# design.net
KiCad netlist of a schematic drawn in Altium Designer
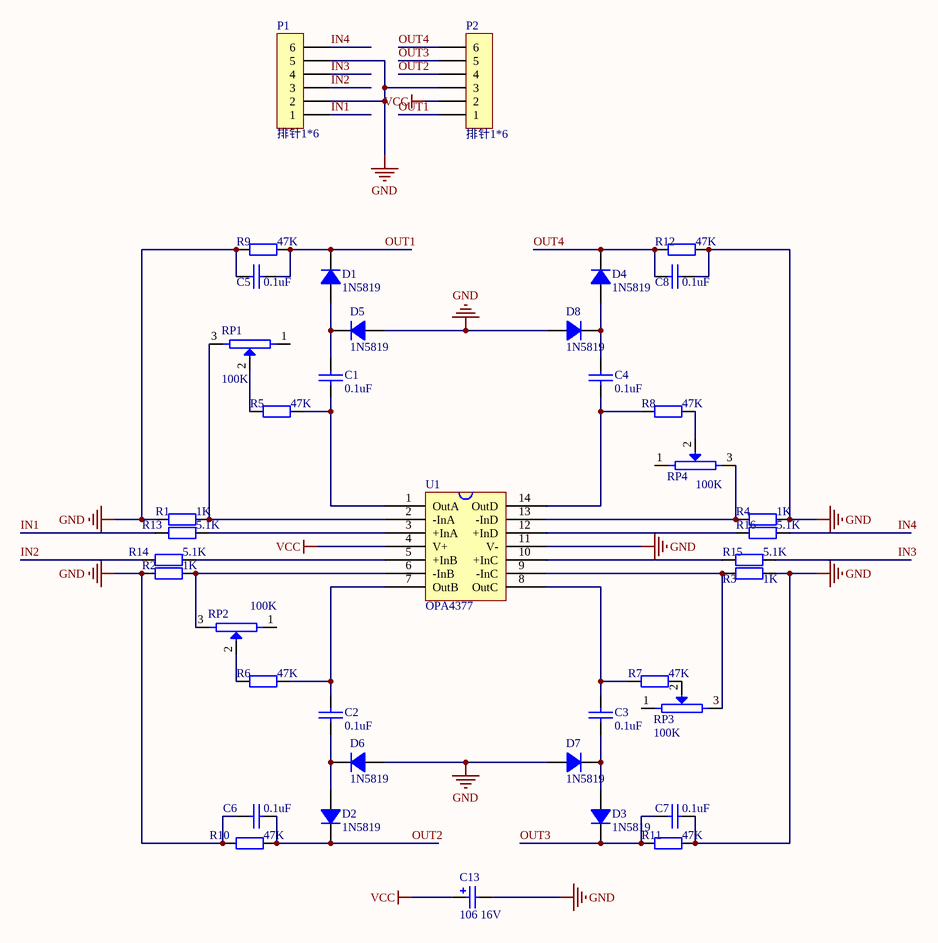
[diagram p0: 运放原理图.SchDoc]

(export (version "E")
  (design (tool "Eeschema 10.0.6"))
  (components
    (comp (ref "C1")
      (value "0.1uF")
      (footprint "C0805")
      (description "Capacitor")
      (libsource (lib "运放原理图库") (part "普通电容"))
    )
    (comp (ref "C2")
      (value "0.1uF")
      (footprint "C0805")
      (description "Capacitor")
      (libsource (lib "运放原理图库") (part "普通电容"))
    )
    (comp (ref "C3")
      (value "0.1uF")
      (footprint "C0805")
      (description "Capacitor")
      (libsource (lib "运放原理图库") (part "普通电容"))
    )
    (comp (ref "C4")
      (value "0.1uF")
      (footprint "C0805")
      (description "Capacitor")
      (libsource (lib "运放原理图库") (part "普通电容"))
    )
    (comp (ref "C5")
      (value "0.1uF")
      (footprint "C0805")
      (description "Capacitor")
      (libsource (lib "运放原理图库") (part "普通电容"))
    )
    (comp (ref "C6")
      (value "0.1uF")
      (footprint "C0805")
      (description "Capacitor")
      (libsource (lib "运放原理图库") (part "普通电容"))
    )
    (comp (ref "C7")
      (value "0.1uF")
      (footprint "C0805")
      (description "Capacitor")
      (libsource (lib "运放原理图库") (part "普通电容"))
    )
    (comp (ref "C8")
      (value "0.1uF")
      (footprint "C0805")
      (description "Capacitor")
      (libsource (lib "运放原理图库") (part "普通电容"))
    )
    (comp (ref "C13") (value "106 16V") (footprint "Tan-A3216") (libsource (lib "运放原理图库") (part "钽电容")))
    (comp (ref "D1")
      (value "1N5819")
      (footprint "SOD-123")
      (description "1N5819 二极管 Diode")
      (fields (field (name "PUBLISHER") "Altium Limited"))
      (libsource (lib "运放原理图库") (part "1N5819"))
    )
    (comp (ref "D2")
      (value "1N5819")
      (footprint "SOD-123")
      (description "1N5819 二极管 Diode")
      (fields (field (name "PUBLISHER") "Altium Limited"))
      (libsource (lib "运放原理图库") (part "1N5819"))
    )
    (comp (ref "D3")
      (value "1N5819")
      (footprint "SOD-123")
      (description "1N5819 二极管 Diode")
      (fields (field (name "PUBLISHER") "Altium Limited"))
      (libsource (lib "运放原理图库") (part "1N5819"))
    )
    (comp (ref "D4")
      (value "1N5819")
      (footprint "SOD-123")
      (description "1N5819 二极管 Diode")
      (fields (field (name "PUBLISHER") "Altium Limited"))
      (libsource (lib "运放原理图库") (part "1N5819"))
    )
    (comp (ref "D5")
      (value "1N5819")
      (footprint "SOD-123")
      (description "1N5819 二极管 Diode")
      (fields (field (name "PUBLISHER") "Altium Limited"))
      (libsource (lib "运放原理图库") (part "1N5819"))
    )
    (comp (ref "D6")
      (value "1N5819")
      (footprint "SOD-123")
      (description "1N5819 二极管 Diode")
      (fields (field (name "PUBLISHER") "Altium Limited"))
      (libsource (lib "运放原理图库") (part "1N5819"))
    )
    (comp (ref "D7")
      (value "1N5819")
      (footprint "SOD-123")
      (description "1N5819 二极管 Diode")
      (fields (field (name "PUBLISHER") "Altium Limited"))
      (libsource (lib "运放原理图库") (part "1N5819"))
    )
    (comp (ref "D8")
      (value "1N5819")
      (footprint "SOD-123")
      (description "1N5819 二极管 Diode")
      (fields (field (name "PUBLISHER") "Altium Limited"))
      (libsource (lib "运放原理图库") (part "1N5819"))
    )
    (comp (ref "P1")
      (value "排针1*6")
      (footprint "LQ_SIP6")
      (description "Connector")
      (libsource (lib "运放原理图库") (part "CON6"))
    )
    (comp (ref "P2")
      (value "排针1*6")
      (footprint "LQ_SIP6")
      (description "Connector")
      (libsource (lib "") (part "CON6_1"))
    )
    (comp (ref "R1")
      (value "1K")
      (footprint "R0805")
      (description "Resistor")
      (fields (field (name "Comment") "1k") (field (name "PUBLISHER") "Altium Limited"))
      (libsource (lib "运放原理图库") (part "Res2"))
    )
    (comp (ref "R2")
      (value "1K")
      (footprint "R0805")
      (description "Resistor")
      (fields (field (name "Comment") "1k") (field (name "PUBLISHER") "Altium Limited"))
      (libsource (lib "运放原理图库") (part "Res2"))
    )
    (comp (ref "R3")
      (value "1K")
      (footprint "R0805")
      (description "Resistor")
      (fields (field (name "Comment") "1k") (field (name "PUBLISHER") "Altium Limited"))
      (libsource (lib "运放原理图库") (part "Res2"))
    )
    (comp (ref "R4")
      (value "1K")
      (footprint "R0805")
      (description "Resistor")
      (fields (field (name "Comment") "1k") (field (name "PUBLISHER") "Altium Limited"))
      (libsource (lib "运放原理图库") (part "Res2"))
    )
    (comp (ref "R5")
      (value "47K")
      (footprint "R0805")
      (description "Resistor")
      (fields (field (name "Comment") "47k") (field (name "PUBLISHER") "Altium Limited"))
      (libsource (lib "运放原理图库") (part "Res2"))
    )
    (comp (ref "R6")
      (value "47K")
      (footprint "R0805")
      (description "Resistor")
      (fields (field (name "Comment") "47k") (field (name "PUBLISHER") "Altium Limited"))
      (libsource (lib "运放原理图库") (part "Res2"))
    )
    (comp (ref "R7")
      (value "47K")
      (footprint "R0805")
      (description "Resistor")
      (fields (field (name "Comment") "47k") (field (name "PUBLISHER") "Altium Limited"))
      (libsource (lib "运放原理图库") (part "Res2"))
    )
    (comp (ref "R8")
      (value "47K")
      (footprint "R0805")
      (description "Resistor")
      (fields (field (name "Comment") "47k") (field (name "PUBLISHER") "Altium Limited"))
      (libsource (lib "运放原理图库") (part "Res2"))
    )
    (comp (ref "R9")
      (value "47K")
      (footprint "R0805")
      (description "Resistor")
      (fields (field (name "Comment") "47k") (field (name "PUBLISHER") "Altium Limited"))
      (libsource (lib "运放原理图库") (part "Res2"))
    )
    (comp (ref "R10")
      (value "47K")
      (footprint "R0805")
      (description "Resistor")
      (fields (field (name "Comment") "47k") (field (name "PUBLISHER") "Altium Limited"))
      (libsource (lib "运放原理图库") (part "Res2"))
    )
    (comp (ref "R11")
      (value "47K")
      (footprint "R0805")
      (description "Resistor")
      (fields (field (name "Comment") "47k") (field (name "PUBLISHER") "Altium Limited"))
      (libsource (lib "运放原理图库") (part "Res2"))
    )
    (comp (ref "R12")
      (value "47K")
      (footprint "R0805")
      (description "Resistor")
      (fields (field (name "Comment") "47k") (field (name "PUBLISHER") "Altium Limited"))
      (libsource (lib "运放原理图库") (part "Res2"))
    )
    (comp (ref "R13")
      (value "5.1K")
      (footprint "R0805")
      (description "Resistor")
      (fields (field (name "Comment") "5.1k") (field (name "PUBLISHER") "Altium Limited"))
      (libsource (lib "运放原理图库") (part "Res2"))
    )
    (comp (ref "R14")
      (value "5.1K")
      (footprint "R0805")
      (description "Resistor")
      (fields (field (name "Comment") "5.1k") (field (name "PUBLISHER") "Altium Limited"))
      (libsource (lib "运放原理图库") (part "Res2"))
    )
    (comp (ref "R15")
      (value "5.1K")
      (footprint "R0805")
      (description "Resistor")
      (fields (field (name "Comment") "5.1k") (field (name "PUBLISHER") "Altium Limited"))
      (libsource (lib "运放原理图库") (part "Res2"))
    )
    (comp (ref "R16")
      (value "5.1K")
      (footprint "R0805")
      (description "Resistor")
      (fields (field (name "Comment") "5.1k") (field (name "PUBLISHER") "Altium Limited"))
      (libsource (lib "运放原理图库") (part "Res2"))
    )
    (comp (ref "RP1")
      (value "100K")
      (footprint "电位器")
      (description "3端可调电阻")
      (libsource (lib "运放原理图库") (part "VR"))
    )
    (comp (ref "RP2")
      (value "100K")
      (footprint "电位器")
      (description "3端可调电阻")
      (libsource (lib "运放原理图库") (part "VR"))
    )
    (comp (ref "RP3")
      (value "100K")
      (footprint "电位器")
      (description "3端可调电阻")
      (libsource (lib "运放原理图库") (part "VR"))
    )
    (comp (ref "RP4")
      (value "100K")
      (footprint "电位器")
      (description "3端可调电阻")
      (libsource (lib "运放原理图库") (part "VR"))
    )
    (comp (ref "U1")
      (value "OPA4377")
      (footprint "TSSOP14")
      (description "OPA4377 四路轨对轨运放")
      (libsource (lib "运放原理图库") (part "OPA4377"))
    )
  )
  (nets
    (net (code "1") (name "/IN1") (class "Default")
      (node (ref "P1") (pin "1") (pinfunction "1_1") (pintype "passive"))
      (node (ref "R13") (pin "1") (pinfunction "1_1") (pintype "passive"))
    )
    (net (code "2") (name "/IN2") (class "Default")
      (node (ref "P1") (pin "3") (pinfunction "3_3") (pintype "passive"))
      (node (ref "R14") (pin "1") (pinfunction "1_1") (pintype "passive"))
    )
    (net (code "3") (name "/IN3") (class "Default")
      (node (ref "P1") (pin "4") (pinfunction "4_4") (pintype "passive"))
      (node (ref "R15") (pin "2") (pinfunction "2_2") (pintype "passive"))
    )
    (net (code "4") (name "/IN4") (class "Default")
      (node (ref "P1") (pin "6") (pinfunction "6_6") (pintype "passive"))
      (node (ref "R16") (pin "2") (pinfunction "2_2") (pintype "passive"))
    )
    (net (code "5") (name "/OUT1") (class "Default")
      (node (ref "C5") (pin "2") (pinfunction "2_2") (pintype "passive"))
      (node (ref "D1") (pin "K") (pinfunction "K_K") (pintype "passive"))
      (node (ref "P2") (pin "1") (pinfunction "1_1") (pintype "passive"))
      (node (ref "R9") (pin "2") (pinfunction "2_2") (pintype "passive"))
    )
    (net (code "6") (name "/OUT2") (class "Default")
      (node (ref "C6") (pin "1") (pinfunction "1_1") (pintype "passive"))
      (node (ref "D2") (pin "K") (pinfunction "K_K") (pintype "passive"))
      (node (ref "P2") (pin "4") (pinfunction "4_4") (pintype "passive"))
      (node (ref "R10") (pin "2") (pinfunction "2_2") (pintype "passive"))
    )
    (net (code "7") (name "/OUT3") (class "Default")
      (node (ref "C7") (pin "2") (pinfunction "2_2") (pintype "passive"))
      (node (ref "D3") (pin "K") (pinfunction "K_K") (pintype "passive"))
      (node (ref "P2") (pin "5") (pinfunction "5_5") (pintype "passive"))
      (node (ref "R11") (pin "1") (pinfunction "1_1") (pintype "passive"))
    )
    (net (code "8") (name "/OUT4") (class "Default")
      (node (ref "C8") (pin "1") (pinfunction "1_1") (pintype "passive"))
      (node (ref "D4") (pin "K") (pinfunction "K_K") (pintype "passive"))
      (node (ref "P2") (pin "6") (pinfunction "6_6") (pintype "passive"))
      (node (ref "R12") (pin "1") (pinfunction "1_1") (pintype "passive"))
    )
    (net (code "9") (name "GND") (class "Default")
      (node (ref "C13") (pin "2") (pinfunction "2_2") (pintype "passive"))
      (node (ref "C5") (pin "1") (pinfunction "1_1") (pintype "passive"))
      (node (ref "C6") (pin "2") (pinfunction "2_2") (pintype "passive"))
      (node (ref "C7") (pin "1") (pinfunction "1_1") (pintype "passive"))
      (node (ref "C8") (pin "2") (pinfunction "2_2") (pintype "passive"))
      (node (ref "D5") (pin "A") (pinfunction "A_A") (pintype "passive"))
      (node (ref "D6") (pin "A") (pinfunction "A_A") (pintype "passive"))
      (node (ref "D7") (pin "A") (pinfunction "A_A") (pintype "passive"))
      (node (ref "D8") (pin "A") (pinfunction "A_A") (pintype "passive"))
      (node (ref "P1") (pin "2") (pinfunction "2_2") (pintype "passive"))
      (node (ref "P1") (pin "5") (pinfunction "5_5") (pintype "passive"))
      (node (ref "P2") (pin "3") (pinfunction "3_3") (pintype "passive"))
      (node (ref "R1") (pin "1") (pinfunction "1_1") (pintype "passive"))
      (node (ref "R10") (pin "1") (pinfunction "1_1") (pintype "passive"))
      (node (ref "R11") (pin "2") (pinfunction "2_2") (pintype "passive"))
      (node (ref "R12") (pin "2") (pinfunction "2_2") (pintype "passive"))
      (node (ref "R2") (pin "1") (pinfunction "1_1") (pintype "passive"))
      (node (ref "R3") (pin "2") (pinfunction "2_2") (pintype "passive"))
      (node (ref "R4") (pin "2") (pinfunction "2_2") (pintype "passive"))
      (node (ref "R9") (pin "1") (pinfunction "1_1") (pintype "passive"))
      (node (ref "U1") (pin "11") (pinfunction "V-_11") (pintype "passive"))
    )
    (net (code "10") (name "Net-(C1-Pad2)") (class "Default")
      (node (ref "C1") (pin "2") (pinfunction "2_2") (pintype "passive"))
      (node (ref "D1") (pin "A") (pinfunction "A_A") (pintype "passive"))
      (node (ref "D5") (pin "K") (pinfunction "K_K") (pintype "passive"))
    )
    (net (code "11") (name "Net-(C2-Pad2)") (class "Default")
      (node (ref "C2") (pin "2") (pinfunction "2_2") (pintype "passive"))
      (node (ref "D2") (pin "A") (pinfunction "A_A") (pintype "passive"))
      (node (ref "D6") (pin "K") (pinfunction "K_K") (pintype "passive"))
    )
    (net (code "12") (name "Net-(C3-Pad2)") (class "Default")
      (node (ref "C3") (pin "2") (pinfunction "2_2") (pintype "passive"))
      (node (ref "D3") (pin "A") (pinfunction "A_A") (pintype "passive"))
      (node (ref "D7") (pin "K") (pinfunction "K_K") (pintype "passive"))
    )
    (net (code "13") (name "Net-(C4-Pad2)") (class "Default")
      (node (ref "C4") (pin "2") (pinfunction "2_2") (pintype "passive"))
      (node (ref "D4") (pin "A") (pinfunction "A_A") (pintype "passive"))
      (node (ref "D8") (pin "K") (pinfunction "K_K") (pintype "passive"))
    )
    (net (code "14") (name "Net-(R5-Pad1)") (class "Default")
      (node (ref "R5") (pin "1") (pinfunction "1_1") (pintype "passive"))
      (node (ref "RP1") (pin "2") (pinfunction "2_2") (pintype "passive"))
    )
    (net (code "15") (name "Net-(R6-Pad1)") (class "Default")
      (node (ref "R6") (pin "1") (pinfunction "1_1") (pintype "passive"))
      (node (ref "RP2") (pin "2") (pinfunction "2_2") (pintype "passive"))
    )
    (net (code "16") (name "Net-(R7-Pad2)") (class "Default")
      (node (ref "R7") (pin "2") (pinfunction "2_2") (pintype "passive"))
      (node (ref "RP3") (pin "2") (pinfunction "2_2") (pintype "passive"))
    )
    (net (code "17") (name "Net-(R8-Pad2)") (class "Default")
      (node (ref "R8") (pin "2") (pinfunction "2_2") (pintype "passive"))
      (node (ref "RP4") (pin "2") (pinfunction "2_2") (pintype "passive"))
    )
    (net (code "18") (name "Net-(U1-+InA)") (class "Default")
      (node (ref "R13") (pin "2") (pinfunction "2_2") (pintype "passive"))
      (node (ref "U1") (pin "3") (pinfunction "+InA_3") (pintype "passive"))
    )
    (net (code "19") (name "Net-(U1-+InB)") (class "Default")
      (node (ref "R14") (pin "2") (pinfunction "2_2") (pintype "passive"))
      (node (ref "U1") (pin "5") (pinfunction "+InB_5") (pintype "passive"))
    )
    (net (code "20") (name "Net-(U1-+InC)") (class "Default")
      (node (ref "R15") (pin "1") (pinfunction "1_1") (pintype "passive"))
      (node (ref "U1") (pin "10") (pinfunction "+InC_10") (pintype "passive"))
    )
    (net (code "21") (name "Net-(U1-+InD)") (class "Default")
      (node (ref "R16") (pin "1") (pinfunction "1_1") (pintype "passive"))
      (node (ref "U1") (pin "12") (pinfunction "+InD_12") (pintype "passive"))
    )
    (net (code "22") (name "Net-(U1--InA)") (class "Default")
      (node (ref "R1") (pin "2") (pinfunction "2_2") (pintype "passive"))
      (node (ref "RP1") (pin "3") (pinfunction "3_3") (pintype "passive"))
      (node (ref "U1") (pin "2") (pinfunction "-InA_2") (pintype "passive"))
    )
    (net (code "23") (name "Net-(U1--InB)") (class "Default")
      (node (ref "R2") (pin "2") (pinfunction "2_2") (pintype "passive"))
      (node (ref "RP2") (pin "3") (pinfunction "3_3") (pintype "passive"))
      (node (ref "U1") (pin "6") (pinfunction "-InB_6") (pintype "passive"))
    )
    (net (code "24") (name "Net-(U1--InC)") (class "Default")
      (node (ref "R3") (pin "1") (pinfunction "1_1") (pintype "passive"))
      (node (ref "RP3") (pin "3") (pinfunction "3_3") (pintype "passive"))
      (node (ref "U1") (pin "9") (pinfunction "-InC_9") (pintype "passive"))
    )
    (net (code "25") (name "Net-(U1--InD)") (class "Default")
      (node (ref "R4") (pin "1") (pinfunction "1_1") (pintype "passive"))
      (node (ref "RP4") (pin "3") (pinfunction "3_3") (pintype "passive"))
      (node (ref "U1") (pin "13") (pinfunction "-InD_13") (pintype "passive"))
    )
    (net (code "26") (name "Net-(U1-OutA)") (class "Default")
      (node (ref "C1") (pin "1") (pinfunction "1_1") (pintype "passive"))
      (node (ref "R5") (pin "2") (pinfunction "2_2") (pintype "passive"))
      (node (ref "U1") (pin "1") (pinfunction "OutA_1") (pintype "passive"))
    )
    (net (code "27") (name "Net-(U1-OutB)") (class "Default")
      (node (ref "C2") (pin "1") (pinfunction "1_1") (pintype "passive"))
      (node (ref "R6") (pin "2") (pinfunction "2_2") (pintype "passive"))
      (node (ref "U1") (pin "7") (pinfunction "OutB_7") (pintype "passive"))
    )
    (net (code "28") (name "Net-(U1-OutC)") (class "Default")
      (node (ref "C3") (pin "1") (pinfunction "1_1") (pintype "passive"))
      (node (ref "R7") (pin "1") (pinfunction "1_1") (pintype "passive"))
      (node (ref "U1") (pin "8") (pinfunction "OutC_8") (pintype "passive"))
    )
    (net (code "29") (name "Net-(U1-OutD)") (class "Default")
      (node (ref "C4") (pin "1") (pinfunction "1_1") (pintype "passive"))
      (node (ref "R8") (pin "1") (pinfunction "1_1") (pintype "passive"))
      (node (ref "U1") (pin "14") (pinfunction "OutD_14") (pintype "passive"))
    )
    (net (code "30") (name "VCC") (class "Default")
      (node (ref "C13") (pin "1") (pinfunction "1_1") (pintype "passive"))
      (node (ref "P2") (pin "2") (pinfunction "2_2") (pintype "passive"))
      (node (ref "U1") (pin "4") (pinfunction "V+_4") (pintype "passive"))
    )
    (net (code "31") (name "unconnected-(RP1-Pad1)") (class "Default")
      (node (ref "RP1") (pin "1") (pinfunction "1_1") (pintype "passive"))
    )
    (net (code "32") (name "unconnected-(RP2-Pad1)") (class "Default")
      (node (ref "RP2") (pin "1") (pinfunction "1_1") (pintype "passive"))
    )
    (net (code "33") (name "unconnected-(RP3-Pad1)") (class "Default")
      (node (ref "RP3") (pin "1") (pinfunction "1_1") (pintype "passive"))
    )
    (net (code "34") (name "unconnected-(RP4-Pad1)") (class "Default")
      (node (ref "RP4") (pin "1") (pinfunction "1_1") (pintype "passive"))
    )
  )
)
